# 08_-_OUTPUT.net
KiCad netlist of a schematic drawn in Altium Designer
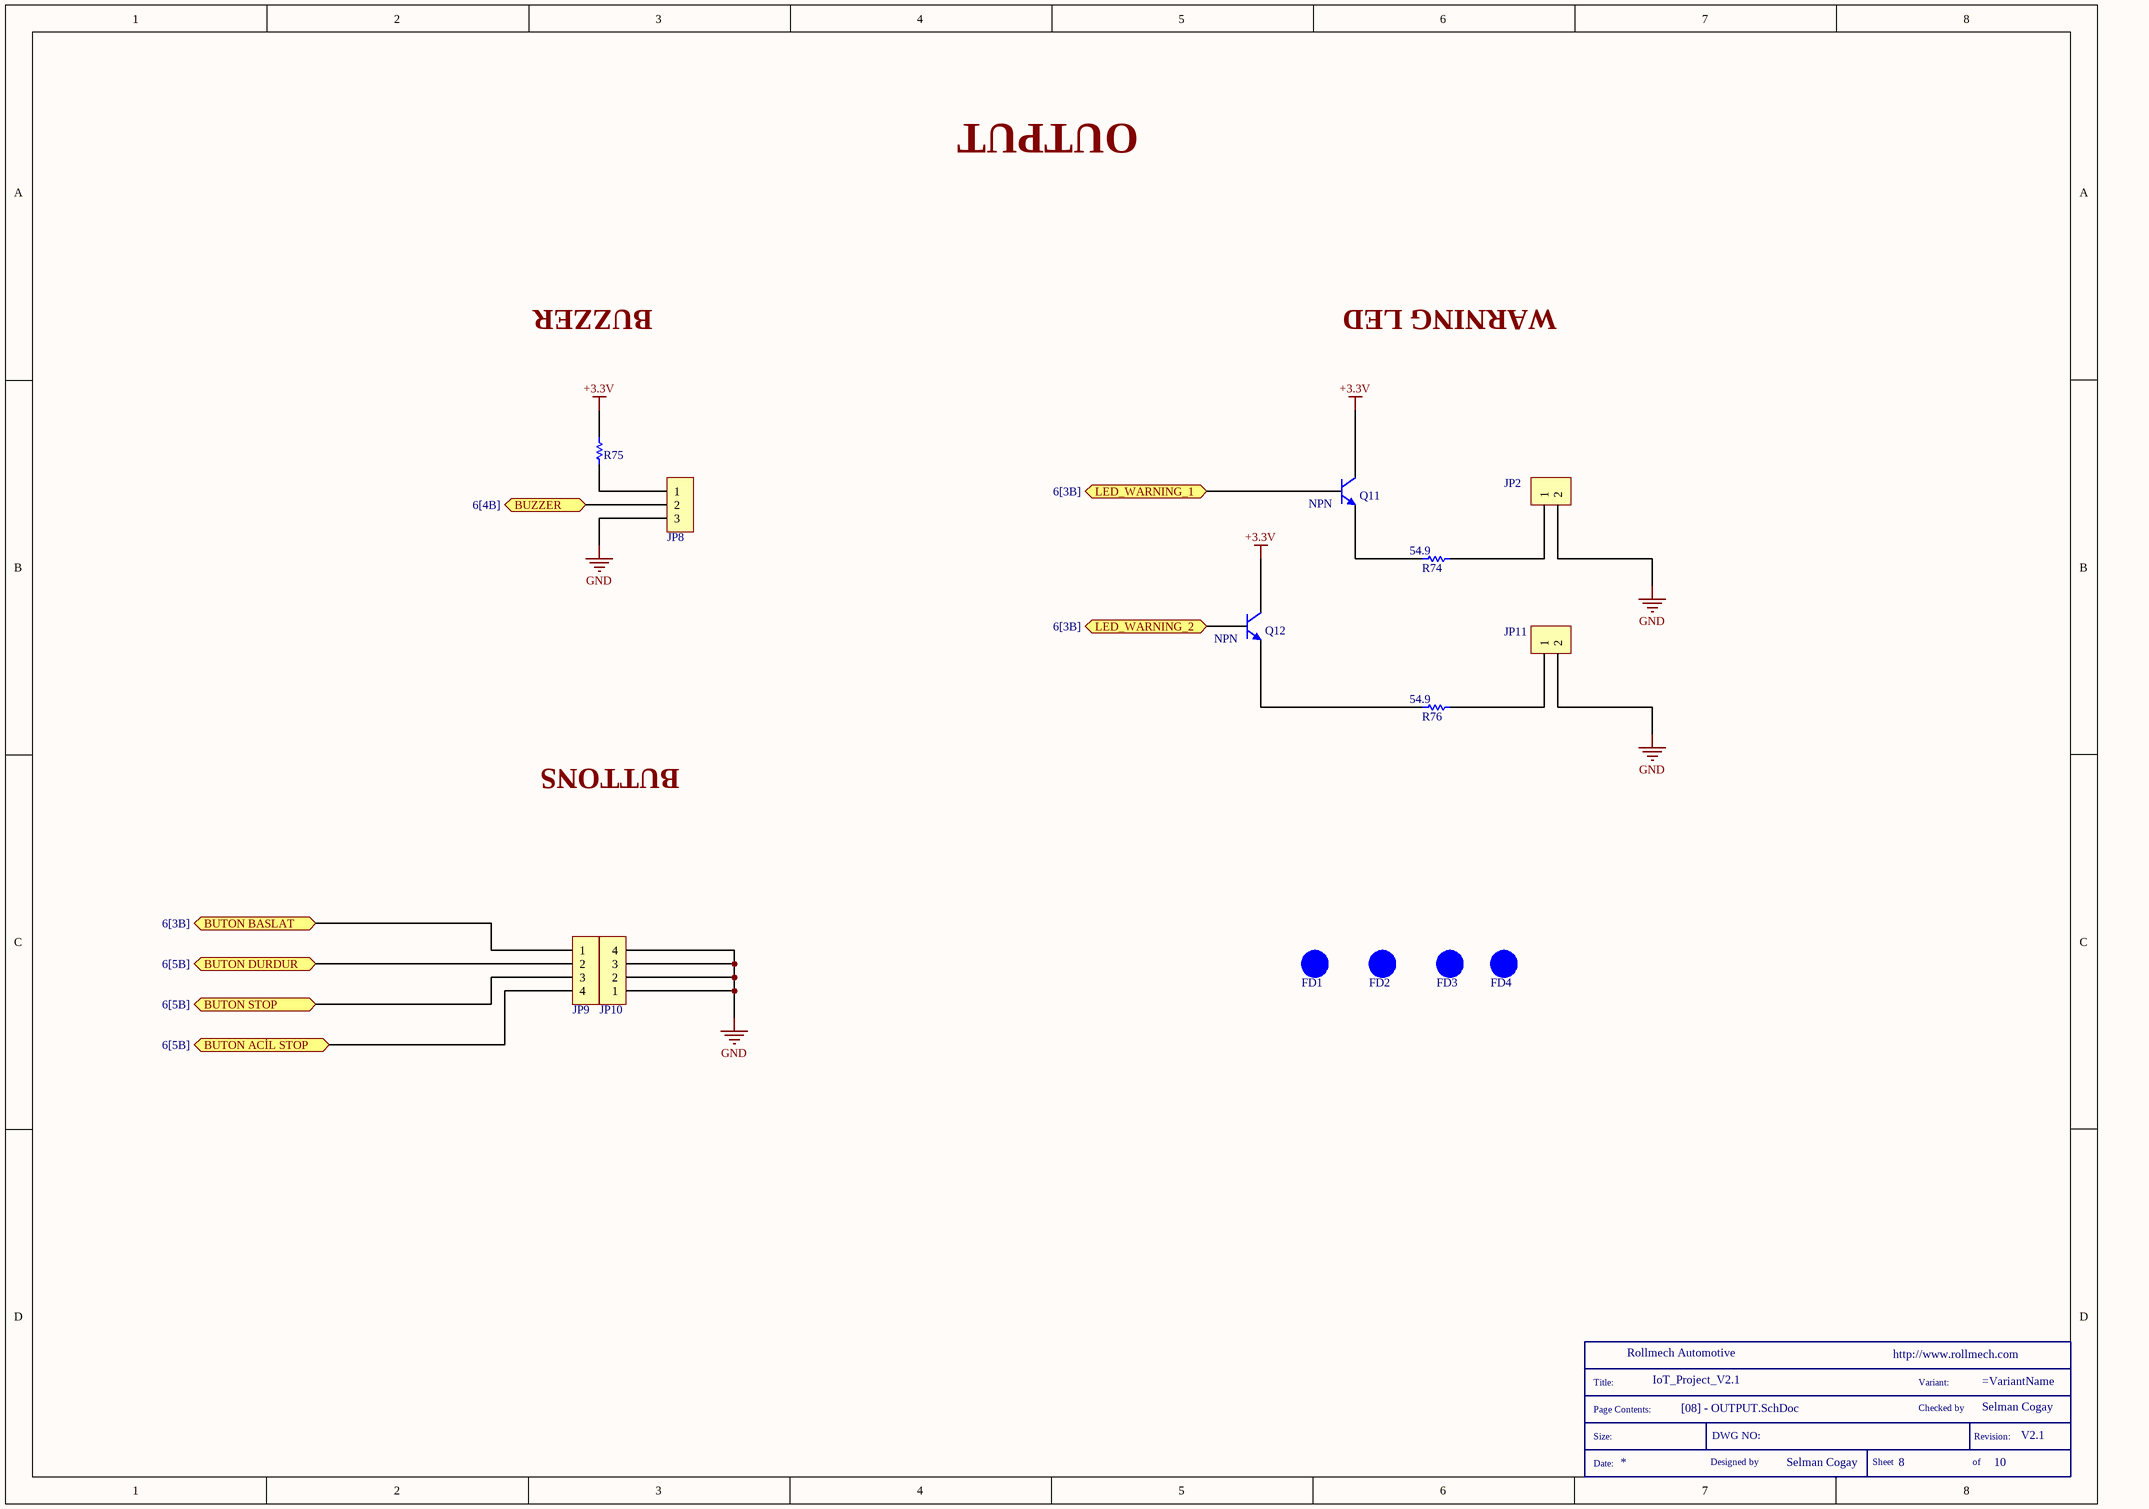
[diagram p0: [08] - OUTPUT.SchDoc]

(export (version "E")
  (design (tool "Eeschema 10.0.6"))
  (components
    (comp (ref "FD1")
      (value "FID_1MMC")
      (footprint "FID_40x120D")
      (description "Fiducial 40 mil diameter , 120 mil mask")
      (libsource (lib "Rollmech_Altium") (part "FID_1MMC"))
    )
    (comp (ref "FD2")
      (value "FID_1MMC")
      (footprint "FID_40x120D")
      (description "Fiducial 40 mil diameter , 120 mil mask")
      (libsource (lib "Rollmech_Altium") (part "FID_1MMC"))
    )
    (comp (ref "FD3")
      (value "FID_1MMC")
      (footprint "FID_40x120D")
      (description "Fiducial 40 mil diameter , 120 mil mask")
      (libsource (lib "Rollmech_Altium") (part "FID_1MMC"))
    )
    (comp (ref "FD4")
      (value "FID_1MMC")
      (footprint "FID_40x120D")
      (description "Fiducial 40 mil diameter , 120 mil mask")
      (libsource (lib "Rollmech_Altium") (part "FID_1MMC"))
    )
    (comp (ref "JP2")
      (value "HDR 1X2 2.54MM")
      (footprint "HDR_FEMALE_1X2_2.54MM")
      (description "HDR FEMALE 1X2 2.54MM")
      (libsource (lib "Rollmech_Altium") (part "PPTC021LFBN-RC"))
    )
    (comp (ref "JP8")
      (value "HDR_1X3_2.54")
      (footprint "HDR_MALE_1X3_2.54MM")
      (description "HDR MALE 1X3 2.54MM")
      (libsource (lib "Rollmech_Altium") (part "61300311121"))
    )
    (comp (ref "JP9")
      (value "HDR FEMALE 1X4 2.54MM")
      (footprint "HDR_FEMALE_1X4_2.54MM")
      (libsource (lib "") (part "PPTC041LFBN-RC_1"))
    )
    (comp (ref "JP10")
      (value "HDR FEMALE 1X4 2.54MM")
      (footprint "HDR_FEMALE_1X4_2.54MM")
      (libsource (lib "Rollmech_Altium") (part "PPTC041LFBN-RC"))
    )
    (comp (ref "JP11")
      (value "HDR 1X2 2.54MM")
      (footprint "HDR_FEMALE_1X2_2.54MM")
      (description "HDR FEMALE 1X2 2.54MM")
      (libsource (lib "Rollmech_Altium") (part "PPTC021LFBN-RC"))
    )
    (comp (ref "Q11")
      (value "NPN")
      (footprint "SOT-23 (TO-236)")
      (description "TRANS NPN 40V 0.6A SMD SOT23-3")
      (libsource (lib "Rollmech_Altium") (part "MMBT2222A-7-F"))
    )
    (comp (ref "Q12")
      (value "NPN")
      (footprint "SOT-23 (TO-236)")
      (description "TRANS NPN 40V 0.6A SMD SOT23-3")
      (libsource (lib "Rollmech_Altium") (part "MMBT2222A-7-F"))
    )
    (comp (ref "R74")
      (value "54.9")
      (footprint "RES_0805")
      (description "RES SMD 54.9 OHM")
      (libsource (lib "Rollmech_Altium") (part "ERJ-6ENF54R9V"))
    )
    (comp (ref "R75")
      (value "0 1/8W")
      (footprint "RES_0805")
      (description "RES SMD 0 OHM JUMPER 1/8W 0805")
      (libsource (lib "Rollmech_Altium") (part "CRCW08050000Z0EA{dblquote}"))
    )
    (comp (ref "R76")
      (value "54.9")
      (footprint "RES_0805")
      (description "RES SMD 54.9 OHM")
      (libsource (lib "Rollmech_Altium") (part "ERJ-6ENF54R9V"))
    )
  )
  (nets
    (net (code "1") (name "+3.3V") (class "Default")
      (node (ref "Q11") (pin "1") (pinfunction "C_1") (pintype "passive"))
      (node (ref "Q12") (pin "1") (pinfunction "C_1") (pintype "passive"))
      (node (ref "R75") (pin "2") (pinfunction "2_2") (pintype "passive"))
    )
    (net (code "2") (name "/BUTON ACİL STOP") (class "Default")
      (node (ref "JP9") (pin "4") (pinfunction "4_4") (pintype "passive"))
    )
    (net (code "3") (name "/BUTON BASLAT") (class "Default")
      (node (ref "JP9") (pin "1") (pinfunction "1_1") (pintype "passive"))
    )
    (net (code "4") (name "/BUTON DURDUR") (class "Default")
      (node (ref "JP9") (pin "2") (pinfunction "2_2") (pintype "passive"))
    )
    (net (code "5") (name "/BUTON STOP") (class "Default")
      (node (ref "JP9") (pin "3") (pinfunction "3_3") (pintype "passive"))
    )
    (net (code "6") (name "/BUZZER") (class "Default")
      (node (ref "JP8") (pin "2") (pinfunction "2_2") (pintype "passive"))
    )
    (net (code "7") (name "/LED_WARNING_1") (class "Default")
      (node (ref "Q11") (pin "2") (pinfunction "B_2") (pintype "passive"))
    )
    (net (code "8") (name "/LED_WARNING_2") (class "Default")
      (node (ref "Q12") (pin "2") (pinfunction "B_2") (pintype "passive"))
    )
    (net (code "9") (name "GND") (class "Default")
      (node (ref "JP10") (pin "1") (pinfunction "1_1") (pintype "passive"))
      (node (ref "JP10") (pin "2") (pinfunction "2_2") (pintype "passive"))
      (node (ref "JP10") (pin "3") (pinfunction "3_3") (pintype "passive"))
      (node (ref "JP10") (pin "4") (pinfunction "4_4") (pintype "passive"))
      (node (ref "JP11") (pin "2") (pinfunction "2_2") (pintype "passive"))
      (node (ref "JP2") (pin "2") (pinfunction "2_2") (pintype "passive"))
      (node (ref "JP8") (pin "3") (pinfunction "3_3") (pintype "passive"))
    )
    (net (code "10") (name "Net-(JP2-Pad1)") (class "Default")
      (node (ref "JP2") (pin "1") (pinfunction "1_1") (pintype "passive"))
      (node (ref "R74") (pin "2") (pinfunction "2_2") (pintype "passive"))
    )
    (net (code "11") (name "Net-(JP8-Pad1)") (class "Default")
      (node (ref "JP8") (pin "1") (pinfunction "1_1") (pintype "passive"))
      (node (ref "R75") (pin "1") (pinfunction "1_1") (pintype "passive"))
    )
    (net (code "12") (name "Net-(JP11-Pad1)") (class "Default")
      (node (ref "JP11") (pin "1") (pinfunction "1_1") (pintype "passive"))
      (node (ref "R76") (pin "2") (pinfunction "2_2") (pintype "passive"))
    )
    (net (code "13") (name "Net-(Q11-E)") (class "Default")
      (node (ref "Q11") (pin "3") (pinfunction "E_3") (pintype "passive"))
      (node (ref "R74") (pin "1") (pinfunction "1_1") (pintype "passive"))
    )
    (net (code "14") (name "Net-(Q12-E)") (class "Default")
      (node (ref "Q12") (pin "3") (pinfunction "E_3") (pintype "passive"))
      (node (ref "R76") (pin "1") (pinfunction "1_1") (pintype "passive"))
    )
  )
)
